# LilyTiny_PB.net
KiCad netlist of a schematic drawn in EAGLE
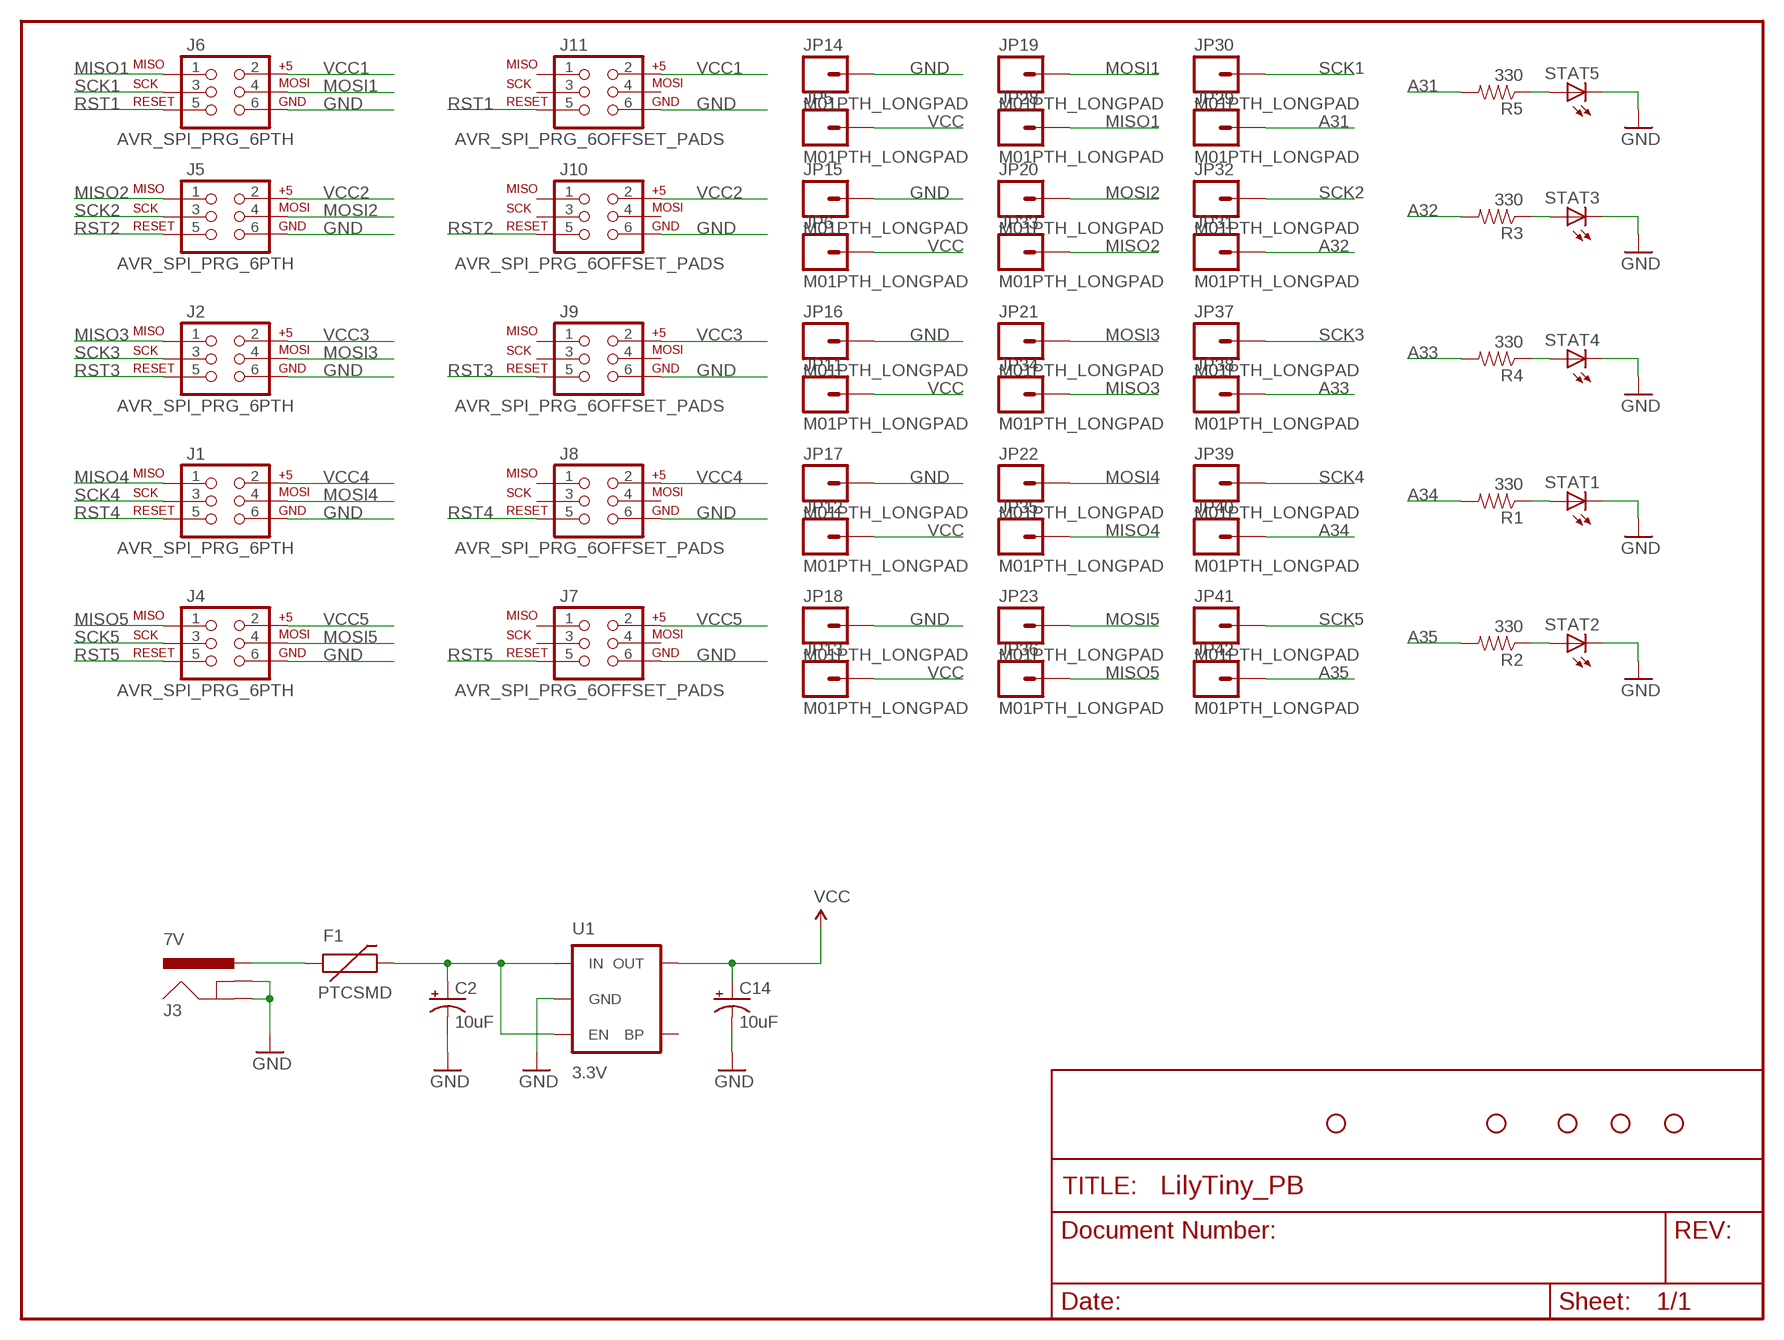
[diagram p0: schematic, sheet 1]

(export (version "E")
  (design (tool "Eeschema 10.0.6"))
  (components
    (comp (ref "C2")
      (value "10uF")
      (footprint "eagle-import:EIA3216")
      (libsource (lib "eagle-import") (part "CAP_POL1206"))
    )
    (comp (ref "C14")
      (value "10uF")
      (footprint "eagle-import:EIA3216")
      (libsource (lib "eagle-import") (part "CAP_POL1206"))
    )
    (comp (ref "F1")
      (value "PTCSMD")
      (footprint "eagle-import:PTC-1206")
      (libsource (lib "eagle-import") (part "PTCSMD"))
    )
    (comp (ref "J1")
      (value "AVR_SPI_PRG_6PTH")
      (footprint "eagle-import:2X3")
      (libsource (lib "eagle-import") (part "AVR_SPI_PRG_6PTH"))
    )
    (comp (ref "J2")
      (value "AVR_SPI_PRG_6PTH")
      (footprint "eagle-import:2X3")
      (libsource (lib "eagle-import") (part "AVR_SPI_PRG_6PTH"))
    )
    (comp (ref "J3")
      (value "7V")
      (footprint "eagle-import:POWER_JACK_PTH_LOCK")
      (libsource (lib "eagle-import") (part "POWER_JACKPTH_LOCK"))
    )
    (comp (ref "J4")
      (value "AVR_SPI_PRG_6PTH")
      (footprint "eagle-import:2X3")
      (libsource (lib "eagle-import") (part "AVR_SPI_PRG_6PTH"))
    )
    (comp (ref "J5")
      (value "AVR_SPI_PRG_6PTH")
      (footprint "eagle-import:2X3")
      (libsource (lib "eagle-import") (part "AVR_SPI_PRG_6PTH"))
    )
    (comp (ref "J6")
      (value "AVR_SPI_PRG_6PTH")
      (footprint "eagle-import:2X3")
      (libsource (lib "eagle-import") (part "AVR_SPI_PRG_6PTH"))
    )
    (comp (ref "J7")
      (value "AVR_SPI_PRG_6OFFSET_PADS")
      (footprint "eagle-import:2X3_OFFSET")
      (libsource (lib "eagle-import") (part "AVR_SPI_PRG_6OFFSET_PADS"))
    )
    (comp (ref "J8")
      (value "AVR_SPI_PRG_6OFFSET_PADS")
      (footprint "eagle-import:2X3_OFFSET")
      (libsource (lib "eagle-import") (part "AVR_SPI_PRG_6OFFSET_PADS"))
    )
    (comp (ref "J9")
      (value "AVR_SPI_PRG_6OFFSET_PADS")
      (footprint "eagle-import:2X3_OFFSET")
      (libsource (lib "eagle-import") (part "AVR_SPI_PRG_6OFFSET_PADS"))
    )
    (comp (ref "J10")
      (value "AVR_SPI_PRG_6OFFSET_PADS")
      (footprint "eagle-import:2X3_OFFSET")
      (libsource (lib "eagle-import") (part "AVR_SPI_PRG_6OFFSET_PADS"))
    )
    (comp (ref "J11")
      (value "AVR_SPI_PRG_6OFFSET_PADS")
      (footprint "eagle-import:2X3_OFFSET")
      (libsource (lib "eagle-import") (part "AVR_SPI_PRG_6OFFSET_PADS"))
    )
    (comp (ref "JP1")
      (value "STAND-OFFTIGHT")
      (footprint "eagle-import:STAND-OFF-TIGHT")
      (libsource (lib "eagle-import") (part "STAND-OFFTIGHT"))
    )
    (comp (ref "JP4")
      (value "STAND-OFFTIGHT")
      (footprint "eagle-import:STAND-OFF-TIGHT")
      (libsource (lib "eagle-import") (part "STAND-OFFTIGHT"))
    )
    (comp (ref "JP5")
      (value "M01PTH_LONGPAD")
      (footprint "eagle-import:1X01_LONGPAD")
      (libsource (lib "eagle-import") (part "M01PTH_LONGPAD"))
    )
    (comp (ref "JP6")
      (value "M01PTH_LONGPAD")
      (footprint "eagle-import:1X01_LONGPAD")
      (libsource (lib "eagle-import") (part "M01PTH_LONGPAD"))
    )
    (comp (ref "JP10")
      (value "STAND-OFFTIGHT")
      (footprint "eagle-import:STAND-OFF-TIGHT")
      (libsource (lib "eagle-import") (part "STAND-OFFTIGHT"))
    )
    (comp (ref "JP11")
      (value "M01PTH_LONGPAD")
      (footprint "eagle-import:1X01_LONGPAD")
      (libsource (lib "eagle-import") (part "M01PTH_LONGPAD"))
    )
    (comp (ref "JP12")
      (value "M01PTH_LONGPAD")
      (footprint "eagle-import:1X01_LONGPAD")
      (libsource (lib "eagle-import") (part "M01PTH_LONGPAD"))
    )
    (comp (ref "JP13")
      (value "M01PTH_LONGPAD")
      (footprint "eagle-import:1X01_LONGPAD")
      (libsource (lib "eagle-import") (part "M01PTH_LONGPAD"))
    )
    (comp (ref "JP14")
      (value "M01PTH_LONGPAD")
      (footprint "eagle-import:1X01_LONGPAD")
      (libsource (lib "eagle-import") (part "M01PTH_LONGPAD"))
    )
    (comp (ref "JP15")
      (value "M01PTH_LONGPAD")
      (footprint "eagle-import:1X01_LONGPAD")
      (libsource (lib "eagle-import") (part "M01PTH_LONGPAD"))
    )
    (comp (ref "JP16")
      (value "M01PTH_LONGPAD")
      (footprint "eagle-import:1X01_LONGPAD")
      (libsource (lib "eagle-import") (part "M01PTH_LONGPAD"))
    )
    (comp (ref "JP17")
      (value "M01PTH_LONGPAD")
      (footprint "eagle-import:1X01_LONGPAD")
      (libsource (lib "eagle-import") (part "M01PTH_LONGPAD"))
    )
    (comp (ref "JP18")
      (value "M01PTH_LONGPAD")
      (footprint "eagle-import:1X01_LONGPAD")
      (libsource (lib "eagle-import") (part "M01PTH_LONGPAD"))
    )
    (comp (ref "JP19")
      (value "M01PTH_LONGPAD")
      (footprint "eagle-import:1X01_LONGPAD")
      (libsource (lib "eagle-import") (part "M01PTH_LONGPAD"))
    )
    (comp (ref "JP20")
      (value "M01PTH_LONGPAD")
      (footprint "eagle-import:1X01_LONGPAD")
      (libsource (lib "eagle-import") (part "M01PTH_LONGPAD"))
    )
    (comp (ref "JP21")
      (value "M01PTH_LONGPAD")
      (footprint "eagle-import:1X01_LONGPAD")
      (libsource (lib "eagle-import") (part "M01PTH_LONGPAD"))
    )
    (comp (ref "JP22")
      (value "M01PTH_LONGPAD")
      (footprint "eagle-import:1X01_LONGPAD")
      (libsource (lib "eagle-import") (part "M01PTH_LONGPAD"))
    )
    (comp (ref "JP23")
      (value "M01PTH_LONGPAD")
      (footprint "eagle-import:1X01_LONGPAD")
      (libsource (lib "eagle-import") (part "M01PTH_LONGPAD"))
    )
    (comp (ref "JP25")
      (value "STAND-OFFTIGHT")
      (footprint "eagle-import:STAND-OFF-TIGHT")
      (libsource (lib "eagle-import") (part "STAND-OFFTIGHT"))
    )
    (comp (ref "JP26")
      (value "STAND-OFFTIGHT")
      (footprint "eagle-import:STAND-OFF-TIGHT")
      (libsource (lib "eagle-import") (part "STAND-OFFTIGHT"))
    )
    (comp (ref "JP28")
      (value "M01PTH_LONGPAD")
      (footprint "eagle-import:1X01_LONGPAD")
      (libsource (lib "eagle-import") (part "M01PTH_LONGPAD"))
    )
    (comp (ref "JP29")
      (value "M01PTH_LONGPAD")
      (footprint "eagle-import:1X01_LONGPAD")
      (libsource (lib "eagle-import") (part "M01PTH_LONGPAD"))
    )
    (comp (ref "JP30")
      (value "M01PTH_LONGPAD")
      (footprint "eagle-import:1X01_LONGPAD")
      (libsource (lib "eagle-import") (part "M01PTH_LONGPAD"))
    )
    (comp (ref "JP31")
      (value "M01PTH_LONGPAD")
      (footprint "eagle-import:1X01_LONGPAD")
      (libsource (lib "eagle-import") (part "M01PTH_LONGPAD"))
    )
    (comp (ref "JP32")
      (value "M01PTH_LONGPAD")
      (footprint "eagle-import:1X01_LONGPAD")
      (libsource (lib "eagle-import") (part "M01PTH_LONGPAD"))
    )
    (comp (ref "JP33")
      (value "M01PTH_LONGPAD")
      (footprint "eagle-import:1X01_LONGPAD")
      (libsource (lib "eagle-import") (part "M01PTH_LONGPAD"))
    )
    (comp (ref "JP34")
      (value "M01PTH_LONGPAD")
      (footprint "eagle-import:1X01_LONGPAD")
      (libsource (lib "eagle-import") (part "M01PTH_LONGPAD"))
    )
    (comp (ref "JP35")
      (value "M01PTH_LONGPAD")
      (footprint "eagle-import:1X01_LONGPAD")
      (libsource (lib "eagle-import") (part "M01PTH_LONGPAD"))
    )
    (comp (ref "JP36")
      (value "M01PTH_LONGPAD")
      (footprint "eagle-import:1X01_LONGPAD")
      (libsource (lib "eagle-import") (part "M01PTH_LONGPAD"))
    )
    (comp (ref "JP37")
      (value "M01PTH_LONGPAD")
      (footprint "eagle-import:1X01_LONGPAD")
      (libsource (lib "eagle-import") (part "M01PTH_LONGPAD"))
    )
    (comp (ref "JP38")
      (value "M01PTH_LONGPAD")
      (footprint "eagle-import:1X01_LONGPAD")
      (libsource (lib "eagle-import") (part "M01PTH_LONGPAD"))
    )
    (comp (ref "JP39")
      (value "M01PTH_LONGPAD")
      (footprint "eagle-import:1X01_LONGPAD")
      (libsource (lib "eagle-import") (part "M01PTH_LONGPAD"))
    )
    (comp (ref "JP40")
      (value "M01PTH_LONGPAD")
      (footprint "eagle-import:1X01_LONGPAD")
      (libsource (lib "eagle-import") (part "M01PTH_LONGPAD"))
    )
    (comp (ref "JP41")
      (value "M01PTH_LONGPAD")
      (footprint "eagle-import:1X01_LONGPAD")
      (libsource (lib "eagle-import") (part "M01PTH_LONGPAD"))
    )
    (comp (ref "JP42")
      (value "M01PTH_LONGPAD")
      (footprint "eagle-import:1X01_LONGPAD")
      (libsource (lib "eagle-import") (part "M01PTH_LONGPAD"))
    )
    (comp (ref "R1")
      (value "330")
      (footprint "eagle-import:0603-RES")
      (libsource (lib "eagle-import") (part "RESISTOR0603-RES"))
    )
    (comp (ref "R2")
      (value "330")
      (footprint "eagle-import:0603-RES")
      (libsource (lib "eagle-import") (part "RESISTOR0603-RES"))
    )
    (comp (ref "R3")
      (value "330")
      (footprint "eagle-import:0603-RES")
      (libsource (lib "eagle-import") (part "RESISTOR0603-RES"))
    )
    (comp (ref "R4")
      (value "330")
      (footprint "eagle-import:0603-RES")
      (libsource (lib "eagle-import") (part "RESISTOR0603-RES"))
    )
    (comp (ref "R5")
      (value "330")
      (footprint "eagle-import:0603-RES")
      (libsource (lib "eagle-import") (part "RESISTOR0603-RES"))
    )
    (comp (ref "STAT1")
      (value "Yellow")
      (footprint "eagle-import:LED-1206")
      (libsource (lib "eagle-import") (part "LED1206"))
    )
    (comp (ref "STAT2")
      (value "Yellow")
      (footprint "eagle-import:LED-1206")
      (libsource (lib "eagle-import") (part "LED1206"))
    )
    (comp (ref "STAT3")
      (value "Yellow")
      (footprint "eagle-import:LED-1206")
      (libsource (lib "eagle-import") (part "LED1206"))
    )
    (comp (ref "STAT4")
      (value "Yellow")
      (footprint "eagle-import:LED-1206")
      (libsource (lib "eagle-import") (part "LED1206"))
    )
    (comp (ref "STAT5")
      (value "Yellow")
      (footprint "eagle-import:LED-1206")
      (libsource (lib "eagle-import") (part "LED1206"))
    )
    (comp (ref "U1")
      (value "3.3V")
      (footprint "eagle-import:SOT23-5")
      (libsource (lib "eagle-import") (part "V_REG_LDOSMD"))
    )
  )
  (nets
    (net (code "1") (name "/A31") (class "Default")
      (node (ref "JP29") (pin "1") (pinfunction "1_1") (pintype "passive"))
      (node (ref "R5") (pin "2") (pinfunction "2_2") (pintype "passive"))
    )
    (net (code "2") (name "/A32") (class "Default")
      (node (ref "JP31") (pin "1") (pinfunction "1_1") (pintype "passive"))
      (node (ref "R3") (pin "2") (pinfunction "2_2") (pintype "passive"))
    )
    (net (code "3") (name "/A33") (class "Default")
      (node (ref "JP38") (pin "1") (pinfunction "1_1") (pintype "passive"))
      (node (ref "R4") (pin "2") (pinfunction "2_2") (pintype "passive"))
    )
    (net (code "4") (name "/A34") (class "Default")
      (node (ref "JP40") (pin "1") (pinfunction "1_1") (pintype "passive"))
      (node (ref "R1") (pin "2") (pinfunction "2_2") (pintype "passive"))
    )
    (net (code "5") (name "/A35") (class "Default")
      (node (ref "JP42") (pin "1") (pinfunction "1_1") (pintype "passive"))
      (node (ref "R2") (pin "2") (pinfunction "2_2") (pintype "passive"))
    )
    (net (code "6") (name "/MISO1") (class "Default")
      (node (ref "J6") (pin "1") (pinfunction "1_1") (pintype "passive"))
      (node (ref "JP28") (pin "1") (pinfunction "1_1") (pintype "passive"))
    )
    (net (code "7") (name "/MISO2") (class "Default")
      (node (ref "J5") (pin "1") (pinfunction "1_1") (pintype "passive"))
      (node (ref "JP33") (pin "1") (pinfunction "1_1") (pintype "passive"))
    )
    (net (code "8") (name "/MISO3") (class "Default")
      (node (ref "J2") (pin "1") (pinfunction "1_1") (pintype "passive"))
      (node (ref "JP34") (pin "1") (pinfunction "1_1") (pintype "passive"))
    )
    (net (code "9") (name "/MISO4") (class "Default")
      (node (ref "J1") (pin "1") (pinfunction "1_1") (pintype "passive"))
      (node (ref "JP35") (pin "1") (pinfunction "1_1") (pintype "passive"))
    )
    (net (code "10") (name "/MISO5") (class "Default")
      (node (ref "J4") (pin "1") (pinfunction "1_1") (pintype "passive"))
      (node (ref "JP36") (pin "1") (pinfunction "1_1") (pintype "passive"))
    )
    (net (code "11") (name "/MOSI1") (class "Default")
      (node (ref "J6") (pin "4") (pinfunction "4_4") (pintype "passive"))
      (node (ref "JP19") (pin "1") (pinfunction "1_1") (pintype "passive"))
    )
    (net (code "12") (name "/MOSI2") (class "Default")
      (node (ref "J5") (pin "4") (pinfunction "4_4") (pintype "passive"))
      (node (ref "JP20") (pin "1") (pinfunction "1_1") (pintype "passive"))
    )
    (net (code "13") (name "/MOSI3") (class "Default")
      (node (ref "J2") (pin "4") (pinfunction "4_4") (pintype "passive"))
      (node (ref "JP21") (pin "1") (pinfunction "1_1") (pintype "passive"))
    )
    (net (code "14") (name "/MOSI4") (class "Default")
      (node (ref "J1") (pin "4") (pinfunction "4_4") (pintype "passive"))
      (node (ref "JP22") (pin "1") (pinfunction "1_1") (pintype "passive"))
    )
    (net (code "15") (name "/MOSI5") (class "Default")
      (node (ref "J4") (pin "4") (pinfunction "4_4") (pintype "passive"))
      (node (ref "JP23") (pin "1") (pinfunction "1_1") (pintype "passive"))
    )
    (net (code "16") (name "/RST1") (class "Default")
      (node (ref "J11") (pin "5") (pinfunction "5_5") (pintype "passive"))
      (node (ref "J6") (pin "5") (pinfunction "5_5") (pintype "passive"))
    )
    (net (code "17") (name "/RST2") (class "Default")
      (node (ref "J10") (pin "5") (pinfunction "5_5") (pintype "passive"))
      (node (ref "J5") (pin "5") (pinfunction "5_5") (pintype "passive"))
    )
    (net (code "18") (name "/RST3") (class "Default")
      (node (ref "J2") (pin "5") (pinfunction "5_5") (pintype "passive"))
      (node (ref "J9") (pin "5") (pinfunction "5_5") (pintype "passive"))
    )
    (net (code "19") (name "/RST4") (class "Default")
      (node (ref "J1") (pin "5") (pinfunction "5_5") (pintype "passive"))
      (node (ref "J8") (pin "5") (pinfunction "5_5") (pintype "passive"))
    )
    (net (code "20") (name "/RST5") (class "Default")
      (node (ref "J4") (pin "5") (pinfunction "5_5") (pintype "passive"))
      (node (ref "J7") (pin "5") (pinfunction "5_5") (pintype "passive"))
    )
    (net (code "21") (name "/SCK1") (class "Default")
      (node (ref "J6") (pin "3") (pinfunction "3_3") (pintype "passive"))
      (node (ref "JP30") (pin "1") (pinfunction "1_1") (pintype "passive"))
    )
    (net (code "22") (name "/SCK2") (class "Default")
      (node (ref "J5") (pin "3") (pinfunction "3_3") (pintype "passive"))
      (node (ref "JP32") (pin "1") (pinfunction "1_1") (pintype "passive"))
    )
    (net (code "23") (name "/SCK3") (class "Default")
      (node (ref "J2") (pin "3") (pinfunction "3_3") (pintype "passive"))
      (node (ref "JP37") (pin "1") (pinfunction "1_1") (pintype "passive"))
    )
    (net (code "24") (name "/SCK4") (class "Default")
      (node (ref "J1") (pin "3") (pinfunction "3_3") (pintype "passive"))
      (node (ref "JP39") (pin "1") (pinfunction "1_1") (pintype "passive"))
    )
    (net (code "25") (name "/SCK5") (class "Default")
      (node (ref "J4") (pin "3") (pinfunction "3_3") (pintype "passive"))
      (node (ref "JP41") (pin "1") (pinfunction "1_1") (pintype "passive"))
    )
    (net (code "26") (name "/VCC1") (class "Default")
      (node (ref "J11") (pin "2") (pinfunction "2_2") (pintype "passive"))
      (node (ref "J6") (pin "2") (pinfunction "2_2") (pintype "passive"))
    )
    (net (code "27") (name "/VCC2") (class "Default")
      (node (ref "J10") (pin "2") (pinfunction "2_2") (pintype "passive"))
      (node (ref "J5") (pin "2") (pinfunction "2_2") (pintype "passive"))
    )
    (net (code "28") (name "/VCC3") (class "Default")
      (node (ref "J2") (pin "2") (pinfunction "2_2") (pintype "passive"))
      (node (ref "J9") (pin "2") (pinfunction "2_2") (pintype "passive"))
    )
    (net (code "29") (name "/VCC4") (class "Default")
      (node (ref "J1") (pin "2") (pinfunction "2_2") (pintype "passive"))
      (node (ref "J8") (pin "2") (pinfunction "2_2") (pintype "passive"))
    )
    (net (code "30") (name "/VCC5") (class "Default")
      (node (ref "J4") (pin "2") (pinfunction "2_2") (pintype "passive"))
      (node (ref "J7") (pin "2") (pinfunction "2_2") (pintype "passive"))
    )
    (net (code "31") (name "GND") (class "Default")
      (node (ref "C14") (pin "C") (pinfunction "-_C") (pintype "passive"))
      (node (ref "C2") (pin "C") (pinfunction "-_C") (pintype "passive"))
      (node (ref "J1") (pin "6") (pinfunction "6_6") (pintype "passive"))
      (node (ref "J10") (pin "6") (pinfunction "6_6") (pintype "passive"))
      (node (ref "J11") (pin "6") (pinfunction "6_6") (pintype "passive"))
      (node (ref "J2") (pin "6") (pinfunction "6_6") (pintype "passive"))
      (node (ref "J3") (pin "GND") (pinfunction "GND_GND") (pintype "bidirectional"))
      (node (ref "J3") (pin "GNDBREAK") (pinfunction "GNDBREAK_GNDBREAK") (pintype "bidirectional"))
      (node (ref "J4") (pin "6") (pinfunction "6_6") (pintype "passive"))
      (node (ref "J5") (pin "6") (pinfunction "6_6") (pintype "passive"))
      (node (ref "J6") (pin "6") (pinfunction "6_6") (pintype "passive"))
      (node (ref "J7") (pin "6") (pinfunction "6_6") (pintype "passive"))
      (node (ref "J8") (pin "6") (pinfunction "6_6") (pintype "passive"))
      (node (ref "J9") (pin "6") (pinfunction "6_6") (pintype "passive"))
      (node (ref "JP14") (pin "1") (pinfunction "1_1") (pintype "passive"))
      (node (ref "JP15") (pin "1") (pinfunction "1_1") (pintype "passive"))
      (node (ref "JP16") (pin "1") (pinfunction "1_1") (pintype "passive"))
      (node (ref "JP17") (pin "1") (pinfunction "1_1") (pintype "passive"))
      (node (ref "JP18") (pin "1") (pinfunction "1_1") (pintype "passive"))
      (node (ref "STAT1") (pin "C") (pinfunction "C_C") (pintype "passive"))
      (node (ref "STAT2") (pin "C") (pinfunction "C_C") (pintype "passive"))
      (node (ref "STAT3") (pin "C") (pinfunction "C_C") (pintype "passive"))
      (node (ref "STAT4") (pin "C") (pinfunction "C_C") (pintype "passive"))
      (node (ref "STAT5") (pin "C") (pinfunction "C_C") (pintype "passive"))
      (node (ref "U1") (pin "2") (pinfunction "GND_2") (pintype "input"))
    )
    (net (code "32") (name "Net-(C2-+)") (class "Default")
      (node (ref "C2") (pin "A") (pinfunction "+_A") (pintype "passive"))
      (node (ref "F1") (pin "2") (pinfunction "2_2") (pintype "bidirectional"))
      (node (ref "U1") (pin "1") (pinfunction "IN_1") (pintype "input"))
      (node (ref "U1") (pin "3") (pinfunction "EN_3") (pintype "input"))
    )
    (net (code "33") (name "Net-(F1-Pad1)") (class "Default")
      (node (ref "F1") (pin "1") (pinfunction "1_1") (pintype "bidirectional"))
      (node (ref "J3") (pin "PWR") (pinfunction "PWR_PWR") (pintype "bidirectional"))
    )
    (net (code "34") (name "Net-(R1-Pad1)") (class "Default")
      (node (ref "R1") (pin "1") (pinfunction "1_1") (pintype "passive"))
      (node (ref "STAT1") (pin "A") (pinfunction "A_A") (pintype "passive"))
    )
    (net (code "35") (name "Net-(R2-Pad1)") (class "Default")
      (node (ref "R2") (pin "1") (pinfunction "1_1") (pintype "passive"))
      (node (ref "STAT2") (pin "A") (pinfunction "A_A") (pintype "passive"))
    )
    (net (code "36") (name "Net-(R3-Pad1)") (class "Default")
      (node (ref "R3") (pin "1") (pinfunction "1_1") (pintype "passive"))
      (node (ref "STAT3") (pin "A") (pinfunction "A_A") (pintype "passive"))
    )
    (net (code "37") (name "Net-(R4-Pad1)") (class "Default")
      (node (ref "R4") (pin "1") (pinfunction "1_1") (pintype "passive"))
      (node (ref "STAT4") (pin "A") (pinfunction "A_A") (pintype "passive"))
    )
    (net (code "38") (name "Net-(R5-Pad1)") (class "Default")
      (node (ref "R5") (pin "1") (pinfunction "1_1") (pintype "passive"))
      (node (ref "STAT5") (pin "A") (pinfunction "A_A") (pintype "passive"))
    )
    (net (code "39") (name "VCC") (class "Default")
      (node (ref "C14") (pin "A") (pinfunction "+_A") (pintype "passive"))
      (node (ref "JP11") (pin "1") (pinfunction "1_1") (pintype "passive"))
      (node (ref "JP12") (pin "1") (pinfunction "1_1") (pintype "passive"))
      (node (ref "JP13") (pin "1") (pinfunction "1_1") (pintype "passive"))
      (node (ref "JP5") (pin "1") (pinfunction "1_1") (pintype "passive"))
      (node (ref "JP6") (pin "1") (pinfunction "1_1") (pintype "passive"))
      (node (ref "U1") (pin "5") (pinfunction "OUT_5") (pintype "passive"))
    )
    (net (code "40") (name "unconnected-(J7-Pad1)") (class "Default")
      (node (ref "J7") (pin "1") (pinfunction "1_1") (pintype "passive"))
    )
    (net (code "41") (name "unconnected-(J7-Pad3)") (class "Default")
      (node (ref "J7") (pin "3") (pinfunction "3_3") (pintype "passive"))
    )
    (net (code "42") (name "unconnected-(J7-Pad4)") (class "Default")
      (node (ref "J7") (pin "4") (pinfunction "4_4") (pintype "passive"))
    )
    (net (code "43") (name "unconnected-(J8-Pad1)") (class "Default")
      (node (ref "J8") (pin "1") (pinfunction "1_1") (pintype "passive"))
    )
    (net (code "44") (name "unconnected-(J8-Pad3)") (class "Default")
      (node (ref "J8") (pin "3") (pinfunction "3_3") (pintype "passive"))
    )
    (net (code "45") (name "unconnected-(J8-Pad4)") (class "Default")
      (node (ref "J8") (pin "4") (pinfunction "4_4") (pintype "passive"))
    )
    (net (code "46") (name "unconnected-(J9-Pad1)") (class "Default")
      (node (ref "J9") (pin "1") (pinfunction "1_1") (pintype "passive"))
    )
    (net (code "47") (name "unconnected-(J9-Pad3)") (class "Default")
      (node (ref "J9") (pin "3") (pinfunction "3_3") (pintype "passive"))
    )
    (net (code "48") (name "unconnected-(J9-Pad4)") (class "Default")
      (node (ref "J9") (pin "4") (pinfunction "4_4") (pintype "passive"))
    )
    (net (code "49") (name "unconnected-(J10-Pad1)") (class "Default")
      (node (ref "J10") (pin "1") (pinfunction "1_1") (pintype "passive"))
    )
    (net (code "50") (name "unconnected-(J10-Pad3)") (class "Default")
      (node (ref "J10") (pin "3") (pinfunction "3_3") (pintype "passive"))
    )
    (net (code "51") (name "unconnected-(J10-Pad4)") (class "Default")
      (node (ref "J10") (pin "4") (pinfunction "4_4") (pintype "passive"))
    )
    (net (code "52") (name "unconnected-(J11-Pad1)") (class "Default")
      (node (ref "J11") (pin "1") (pinfunction "1_1") (pintype "passive"))
    )
    (net (code "53") (name "unconnected-(J11-Pad3)") (class "Default")
      (node (ref "J11") (pin "3") (pinfunction "3_3") (pintype "passive"))
    )
    (net (code "54") (name "unconnected-(J11-Pad4)") (class "Default")
      (node (ref "J11") (pin "4") (pinfunction "4_4") (pintype "passive"))
    )
    (net (code "55") (name "unconnected-(U1-BP-Pad4)") (class "Default")
      (node (ref "U1") (pin "4") (pinfunction "BP_4") (pintype "input"))
    )
  )
)
